# con_brd.net
KiCad netlist of a schematic drawn in EAGLE
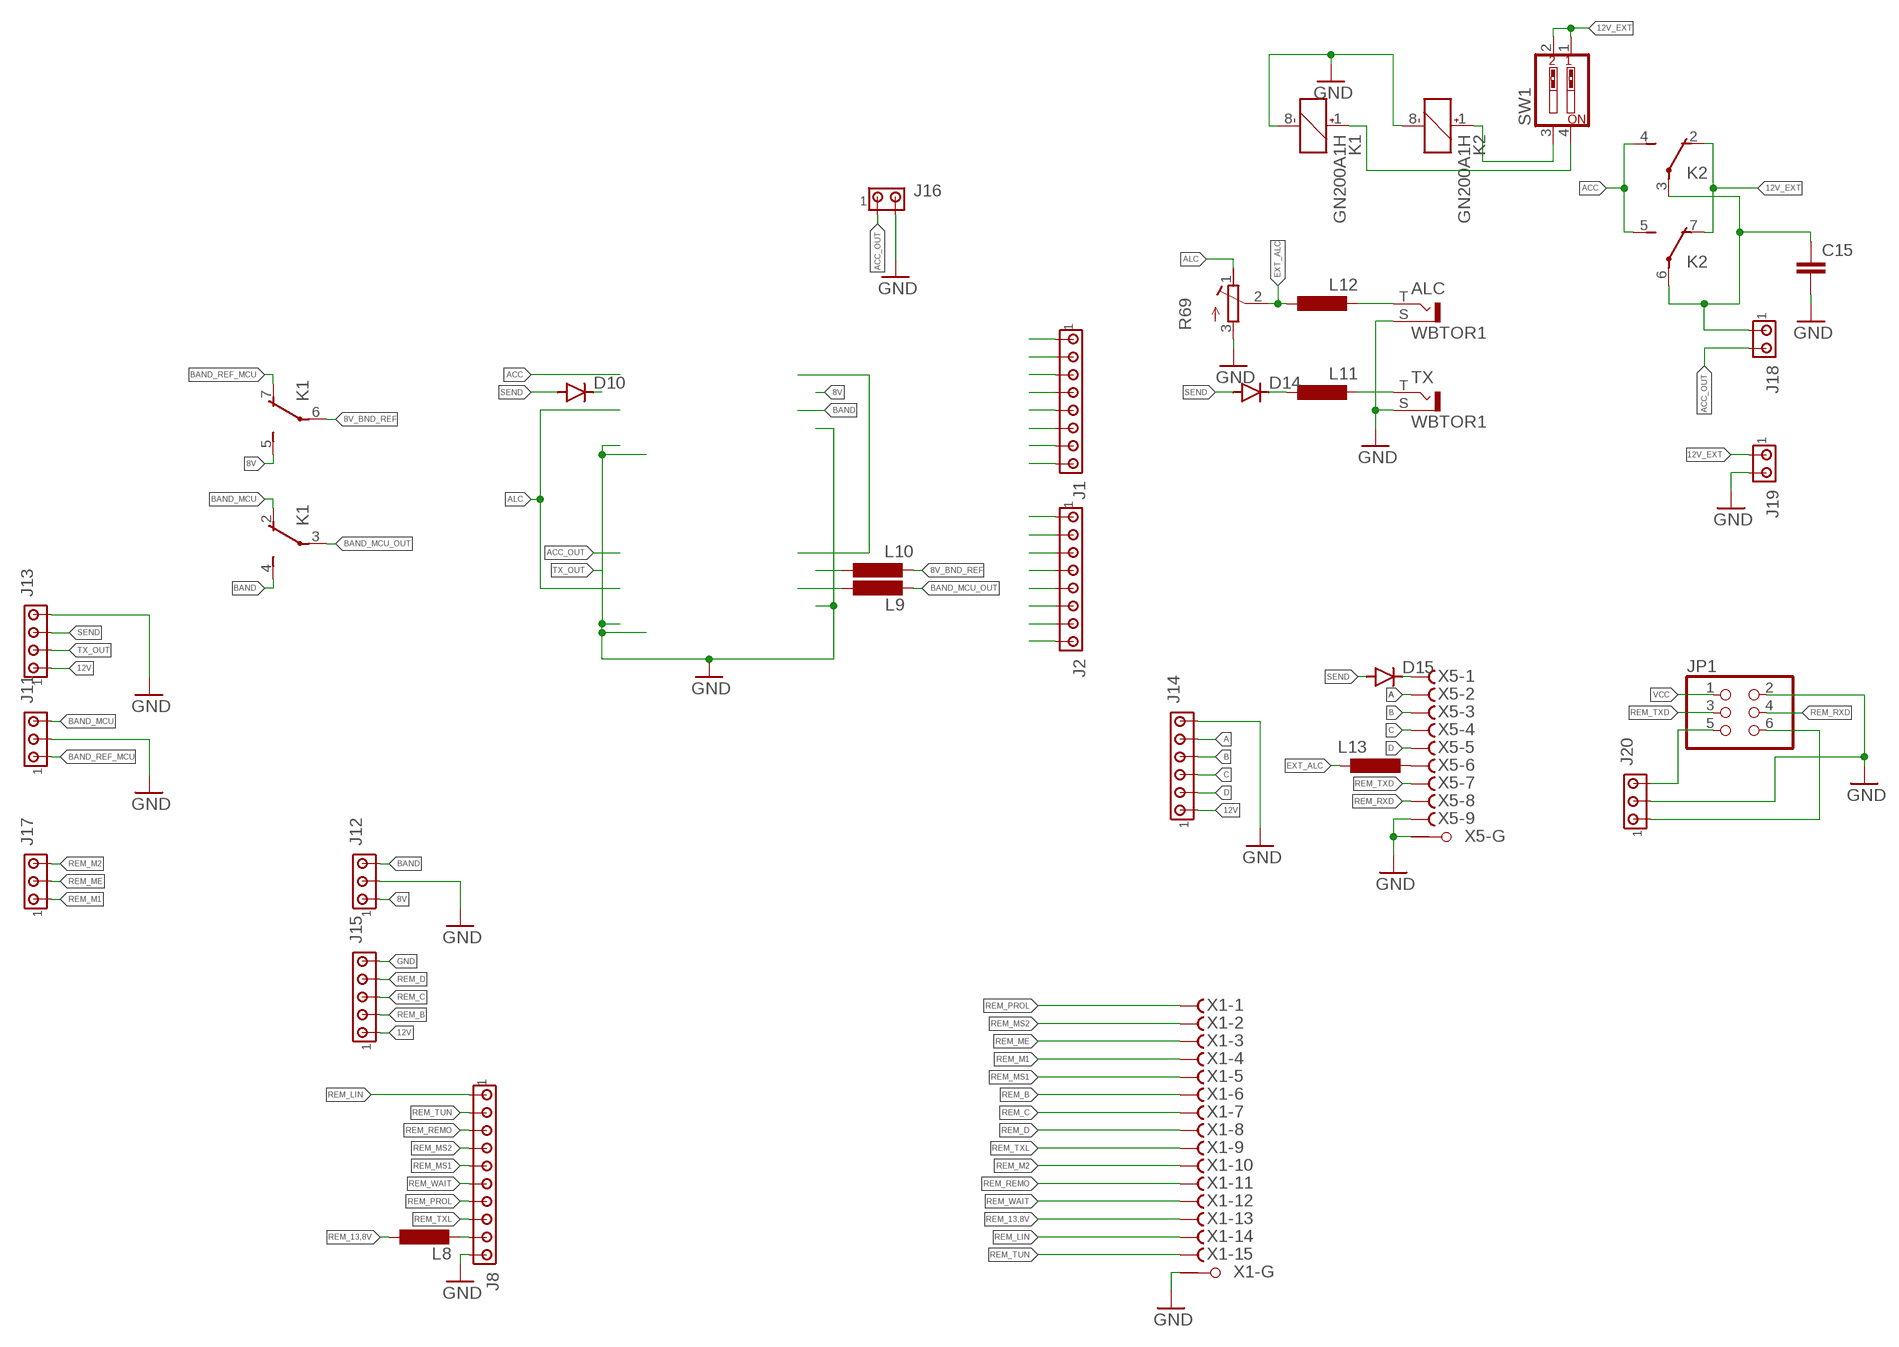
[diagram p0: schematic, sheet 1]

(export (version "E")
  (design (tool "Eeschema 10.0.6"))
  (components
    (comp (ref "ALC")
      (value "WBTOR1")
      (footprint "eagle-import:WBTOR1")
      (fields (field (name "MPN") "WBTOR 1 BLACK"))
      (libsource (lib "eagle-import") (part "WBTOR1"))
    )
    (comp (ref "C15")
      (value "C-EUC0805K")
      (footprint "eagle-import:C0805K")
      (libsource (lib "eagle-import") (part "C-EUC0805K"))
    )
    (comp (ref "D10")
      (value "DIODE-SOD123")
      (footprint "eagle-import:SOD123")
      (libsource (lib "eagle-import") (part "DIODE-SOD123"))
    )
    (comp (ref "D14")
      (value "DIODE-SOD123")
      (footprint "eagle-import:SOD123")
      (libsource (lib "eagle-import") (part "DIODE-SOD123"))
    )
    (comp (ref "D15")
      (value "DIODE-SOD123")
      (footprint "eagle-import:SOD123")
      (libsource (lib "eagle-import") (part "DIODE-SOD123"))
    )
    (comp (ref "J1")
      (value "MTA08-100")
      (footprint "eagle-import:10X08MTA")
      (libsource (lib "eagle-import") (part "MTA08-100"))
    )
    (comp (ref "J2")
      (value "MTA08-100")
      (footprint "eagle-import:10X08MTA")
      (libsource (lib "eagle-import") (part "MTA08-100"))
    )
    (comp (ref "J8")
      (value "MTA10-100")
      (footprint "eagle-import:10X10MTA")
      (libsource (lib "eagle-import") (part "MTA10-100"))
    )
    (comp (ref "J11")
      (value "MTA03-100")
      (footprint "eagle-import:10X03MTA")
      (libsource (lib "eagle-import") (part "MTA03-100"))
    )
    (comp (ref "J12")
      (value "MTA03-100")
      (footprint "eagle-import:10X03MTA")
      (libsource (lib "eagle-import") (part "MTA03-100"))
    )
    (comp (ref "J13")
      (value "MTA04-100")
      (footprint "eagle-import:10X04MTA")
      (libsource (lib "eagle-import") (part "MTA04-100"))
    )
    (comp (ref "J14")
      (value "MTA06-100")
      (footprint "eagle-import:10X06MTA")
      (libsource (lib "eagle-import") (part "MTA06-100"))
    )
    (comp (ref "J15")
      (value "MTA05-100")
      (footprint "eagle-import:10X05MTA")
      (libsource (lib "eagle-import") (part "MTA05-100"))
    )
    (comp (ref "J16")
      (value "MTA02-100")
      (footprint "eagle-import:10X02MTA")
      (libsource (lib "eagle-import") (part "MTA02-100"))
    )
    (comp (ref "J17")
      (value "MTA03-100")
      (footprint "eagle-import:10X03MTA")
      (libsource (lib "eagle-import") (part "MTA03-100"))
    )
    (comp (ref "J18")
      (value "MTA02-100")
      (footprint "eagle-import:10X02MTA")
      (libsource (lib "eagle-import") (part "MTA02-100"))
    )
    (comp (ref "J19")
      (value "MTA02-100")
      (footprint "eagle-import:10X02MTA")
      (libsource (lib "eagle-import") (part "MTA02-100"))
    )
    (comp (ref "J20")
      (value "MTA03-100")
      (footprint "eagle-import:10X03MTA")
      (libsource (lib "eagle-import") (part "MTA03-100"))
    )
    (comp (ref "JP1")
      (value "PINHD-2X3")
      (footprint "eagle-import:2X03")
      (libsource (lib "eagle-import") (part "PINHD-2X3"))
    )
    (comp (ref "K1")
      (value "GN200A1H")
      (footprint "eagle-import:GN-A")
      (libsource (lib "eagle-import") (part "GN?200A1H"))
    )
    (comp (ref "K2")
      (value "GN200A1H")
      (footprint "eagle-import:GN-A")
      (libsource (lib "eagle-import") (part "GN?200A1H"))
    )
    (comp (ref "L8")
      (value "L-EUL3230M")
      (footprint "eagle-import:L3230M")
      (libsource (lib "eagle-import") (part "L-EUL3230M"))
    )
    (comp (ref "L9")
      (value "L-EUL2012C")
      (footprint "eagle-import:L2012C")
      (libsource (lib "eagle-import") (part "L-EUL2012C"))
    )
    (comp (ref "L10")
      (value "L-EUL2012C")
      (footprint "eagle-import:L2012C")
      (libsource (lib "eagle-import") (part "L-EUL2012C"))
    )
    (comp (ref "L11")
      (value "L-EUL2012C")
      (footprint "eagle-import:L2012C")
      (libsource (lib "eagle-import") (part "L-EUL2012C"))
    )
    (comp (ref "L12")
      (value "L-EUL2012C")
      (footprint "eagle-import:L2012C")
      (libsource (lib "eagle-import") (part "L-EUL2012C"))
    )
    (comp (ref "L13")
      (value "L-EUL2012C")
      (footprint "eagle-import:L2012C")
      (libsource (lib "eagle-import") (part "L-EUL2012C"))
    )
    (comp (ref "R69")
      (value "R-TRIMM43P")
      (footprint "eagle-import:RTRIM43P")
      (libsource (lib "eagle-import") (part "R-TRIMM43P"))
    )
    (comp (ref "SW1")
      (value "SW_DIP-2")
      (footprint "eagle-import:EDG-02")
      (libsource (lib "eagle-import") (part "SW_DIP-2"))
    )
    (comp (ref "TX")
      (value "WBTOR1")
      (footprint "eagle-import:WBTOR1")
      (fields (field (name "MPN") "WBTOR 1 BLACK"))
      (libsource (lib "eagle-import") (part "WBTOR1"))
    )
    (comp (ref "X1")
      (value "F15HPS")
      (footprint "eagle-import:F15HP")
      (libsource (lib "eagle-import") (part "F15HPS"))
    )
    (comp (ref "X5")
      (value "F09HPS")
      (footprint "eagle-import:F09HP")
      (libsource (lib "eagle-import") (part "F09HPS"))
    )
  )
  (nets
    (net (code "1") (name "/N$71") (class "Default")
      (node (ref "J1") (pin "6") (pinfunction "6_6") (pintype "passive"))
      (node (ref "J2") (pin "6") (pinfunction "6_6") (pintype "passive"))
    )
    (net (code "2") (name "/N$72") (class "Default")
      (node (ref "J2") (pin "4") (pinfunction "4_4") (pintype "passive"))
      (node (ref "L9") (pin "1") (pinfunction "1_1") (pintype "passive"))
    )
    (net (code "3") (name "/N$75") (class "Default")
      (node (ref "J2") (pin "1") (pinfunction "1_1") (pintype "passive"))
      (node (ref "L10") (pin "1") (pinfunction "1_1") (pintype "passive"))
    )
    (net (code "4") (name "/N$79") (class "Default")
      (node (ref "D10") (pin "C") (pinfunction "C_C") (pintype "passive"))
      (node (ref "J1") (pin "3") (pinfunction "3_3") (pintype "passive"))
    )
    (net (code "5") (name "8V") (class "Default")
      (node (ref "J1") (pin "1") (pinfunction "1_1") (pintype "passive"))
      (node (ref "J12") (pin "1") (pinfunction "1_1") (pintype "passive"))
      (node (ref "K1") (pin "5") (pinfunction "S_5") (pintype "passive"))
    )
    (net (code "6") (name "8V_BND_REF") (class "Default")
      (node (ref "K1") (pin "6") (pinfunction "P_6") (pintype "passive"))
      (node (ref "L10") (pin "2") (pinfunction "2_2") (pintype "passive"))
    )
    (net (code "7") (name "12V") (class "Default")
      (node (ref "J13") (pin "1") (pinfunction "1_1") (pintype "passive"))
      (node (ref "J14") (pin "1") (pinfunction "1_1") (pintype "passive"))
      (node (ref "J15") (pin "1") (pinfunction "1_1") (pintype "passive"))
    )
    (net (code "8") (name "12V_EXT") (class "Default")
      (node (ref "J19") (pin "1") (pinfunction "1_1") (pintype "passive"))
      (node (ref "K2") (pin "2") (pinfunction "O_2") (pintype "passive"))
      (node (ref "K2") (pin "7") (pinfunction "O_7") (pintype "passive"))
      (node (ref "SW1") (pin "1") (pinfunction "1_1") (pintype "passive"))
      (node (ref "SW1") (pin "2") (pinfunction "2_2") (pintype "passive"))
    )
    (net (code "9") (name "A") (class "Default")
      (node (ref "J14") (pin "5") (pinfunction "5_5") (pintype "passive"))
      (node (ref "X5") (pin "2") (pinfunction "F_2") (pintype "passive"))
    )
    (net (code "10") (name "ACC") (class "Default")
      (node (ref "J1") (pin "7") (pinfunction "7_7") (pintype "passive"))
      (node (ref "K2") (pin "4") (pinfunction "S_4") (pintype "passive"))
      (node (ref "K2") (pin "5") (pinfunction "S_5") (pintype "passive"))
    )
    (net (code "11") (name "ACC_OUT") (class "Default")
      (node (ref "J16") (pin "1") (pinfunction "1_1") (pintype "passive"))
      (node (ref "J18") (pin "2") (pinfunction "2_2") (pintype "passive"))
      (node (ref "J2") (pin "7") (pinfunction "7_7") (pintype "passive"))
    )
    (net (code "12") (name "ALC") (class "Default")
      (node (ref "J1") (pin "5") (pinfunction "5_5") (pintype "passive"))
      (node (ref "J2") (pin "5") (pinfunction "5_5") (pintype "passive"))
      (node (ref "R69") (pin "1") (pinfunction "E_1") (pintype "passive"))
    )
    (net (code "13") (name "B") (class "Default")
      (node (ref "J14") (pin "4") (pinfunction "4_4") (pintype "passive"))
      (node (ref "X5") (pin "3") (pinfunction "F_3") (pintype "passive"))
    )
    (net (code "14") (name "BAND") (class "Default")
      (node (ref "J1") (pin "4") (pinfunction "4_4") (pintype "passive"))
      (node (ref "J12") (pin "3") (pinfunction "3_3") (pintype "passive"))
      (node (ref "K1") (pin "4") (pinfunction "S_4") (pintype "passive"))
    )
    (net (code "15") (name "BAND_MCU") (class "Default")
      (node (ref "J11") (pin "3") (pinfunction "3_3") (pintype "passive"))
      (node (ref "K1") (pin "2") (pinfunction "O_2") (pintype "passive"))
    )
    (net (code "16") (name "BAND_MCU_OUT") (class "Default")
      (node (ref "K1") (pin "3") (pinfunction "P_3") (pintype "passive"))
      (node (ref "L9") (pin "2") (pinfunction "2_2") (pintype "passive"))
    )
    (net (code "17") (name "BAND_REF_MCU") (class "Default")
      (node (ref "J11") (pin "1") (pinfunction "1_1") (pintype "passive"))
      (node (ref "K1") (pin "7") (pinfunction "O_7") (pintype "passive"))
    )
    (net (code "18") (name "C") (class "Default")
      (node (ref "J14") (pin "3") (pinfunction "3_3") (pintype "passive"))
      (node (ref "X5") (pin "4") (pinfunction "F_4") (pintype "passive"))
    )
    (net (code "19") (name "D") (class "Default")
      (node (ref "J14") (pin "2") (pinfunction "2_2") (pintype "passive"))
      (node (ref "X5") (pin "5") (pinfunction "F_5") (pintype "passive"))
    )
    (net (code "20") (name "EXT_ALC") (class "Default")
      (node (ref "L12") (pin "1") (pinfunction "1_1") (pintype "passive"))
      (node (ref "L13") (pin "1") (pinfunction "1_1") (pintype "passive"))
      (node (ref "R69") (pin "2") (pinfunction "S_2") (pintype "passive"))
    )
    (net (code "21") (name "GND") (class "Default")
      (node (ref "ALC") (pin "S") (pinfunction "S_S") (pintype "passive"))
      (node (ref "C15") (pin "2") (pinfunction "2_2") (pintype "passive"))
      (node (ref "J1") (pin "2") (pinfunction "2_2") (pintype "passive"))
      (node (ref "J1") (pin "8") (pinfunction "8_8") (pintype "passive"))
      (node (ref "J11") (pin "2") (pinfunction "2_2") (pintype "passive"))
      (node (ref "J12") (pin "2") (pinfunction "2_2") (pintype "passive"))
      (node (ref "J13") (pin "4") (pinfunction "4_4") (pintype "passive"))
      (node (ref "J14") (pin "6") (pinfunction "6_6") (pintype "passive"))
      (node (ref "J15") (pin "5") (pinfunction "5_5") (pintype "passive"))
      (node (ref "J16") (pin "2") (pinfunction "2_2") (pintype "passive"))
      (node (ref "J19") (pin "2") (pinfunction "2_2") (pintype "passive"))
      (node (ref "J2") (pin "2") (pinfunction "2_2") (pintype "passive"))
      (node (ref "J2") (pin "8") (pinfunction "8_8") (pintype "passive"))
      (node (ref "J20") (pin "2") (pinfunction "2_2") (pintype "passive"))
      (node (ref "J8") (pin "10") (pinfunction "10_10") (pintype "passive"))
      (node (ref "JP1") (pin "2") (pinfunction "2_2") (pintype "passive"))
      (node (ref "K1") (pin "8") (pinfunction "-_8") (pintype "passive"))
      (node (ref "K2") (pin "8") (pinfunction "-_8") (pintype "passive"))
      (node (ref "R69") (pin "3") (pinfunction "A_3") (pintype "passive"))
      (node (ref "TX") (pin "S") (pinfunction "S_S") (pintype "passive"))
      (node (ref "X1") (pin "G1") (pinfunction "G1_G1") (pintype "passive"))
      (node (ref "X5") (pin "9") (pinfunction "F_9") (pintype "passive"))
      (node (ref "X5") (pin "G1") (pinfunction "G1_G1") (pintype "passive"))
    )
    (net (code "22") (name "Net-(ALC-PadT)") (class "Default")
      (node (ref "ALC") (pin "T") (pinfunction "T_T") (pintype "passive"))
      (node (ref "L12") (pin "2") (pinfunction "2_2") (pintype "passive"))
    )
    (net (code "23") (name "Net-(D14-PadC)") (class "Default")
      (node (ref "D14") (pin "C") (pinfunction "C_C") (pintype "passive"))
      (node (ref "L11") (pin "1") (pinfunction "1_1") (pintype "passive"))
    )
    (net (code "24") (name "Net-(J8-Pad9)") (class "Default")
      (node (ref "J8") (pin "9") (pinfunction "9_9") (pintype "passive"))
      (node (ref "L8") (pin "2") (pinfunction "2_2") (pintype "passive"))
    )
    (net (code "25") (name "Net-(J20-Pad1)") (class "Default")
      (node (ref "J20") (pin "1") (pinfunction "1_1") (pintype "passive"))
      (node (ref "JP1") (pin "6") (pinfunction "6_6") (pintype "passive"))
    )
    (net (code "26") (name "Net-(J20-Pad3)") (class "Default")
      (node (ref "J20") (pin "3") (pinfunction "3_3") (pintype "passive"))
      (node (ref "JP1") (pin "5") (pinfunction "5_5") (pintype "passive"))
    )
    (net (code "27") (name "Net-(K1A-+)") (class "Default")
      (node (ref "K1") (pin "1") (pinfunction "+_1") (pintype "passive"))
      (node (ref "SW1") (pin "4") (pinfunction "4_4") (pintype "passive"))
    )
    (net (code "28") (name "Net-(K2A-+)") (class "Default")
      (node (ref "K2") (pin "1") (pinfunction "+_1") (pintype "passive"))
      (node (ref "SW1") (pin "3") (pinfunction "3_3") (pintype "passive"))
    )
    (net (code "29") (name "Net-(L11-Pad2)") (class "Default")
      (node (ref "L11") (pin "2") (pinfunction "2_2") (pintype "passive"))
      (node (ref "TX") (pin "T") (pinfunction "T_T") (pintype "passive"))
    )
    (net (code "30") (name "Net-(X5A-F)") (class "Default")
      (node (ref "D15") (pin "C") (pinfunction "C_C") (pintype "passive"))
      (node (ref "X5") (pin "1") (pinfunction "F_1") (pintype "passive"))
    )
    (net (code "31") (name "Net-(X5F-F)") (class "Default")
      (node (ref "L13") (pin "2") (pinfunction "2_2") (pintype "passive"))
      (node (ref "X5") (pin "6") (pinfunction "F_6") (pintype "passive"))
    )
    (net (code "32") (name "REM_13,8V") (class "Default")
      (node (ref "L8") (pin "1") (pinfunction "1_1") (pintype "passive"))
      (node (ref "X1") (pin "13") (pinfunction "F_13") (pintype "passive"))
    )
    (net (code "33") (name "REM_B") (class "Default")
      (node (ref "J15") (pin "2") (pinfunction "2_2") (pintype "passive"))
      (node (ref "X1") (pin "6") (pinfunction "F_6") (pintype "passive"))
    )
    (net (code "34") (name "REM_C") (class "Default")
      (node (ref "J15") (pin "3") (pinfunction "3_3") (pintype "passive"))
      (node (ref "X1") (pin "7") (pinfunction "F_7") (pintype "passive"))
    )
    (net (code "35") (name "REM_D") (class "Default")
      (node (ref "J15") (pin "4") (pinfunction "4_4") (pintype "passive"))
      (node (ref "X1") (pin "8") (pinfunction "F_8") (pintype "passive"))
    )
    (net (code "36") (name "REM_LIN") (class "Default")
      (node (ref "J8") (pin "1") (pinfunction "1_1") (pintype "passive"))
      (node (ref "X1") (pin "14") (pinfunction "F_14") (pintype "passive"))
    )
    (net (code "37") (name "REM_M1") (class "Default")
      (node (ref "J17") (pin "1") (pinfunction "1_1") (pintype "passive"))
      (node (ref "X1") (pin "4") (pinfunction "F_4") (pintype "passive"))
    )
    (net (code "38") (name "REM_M2") (class "Default")
      (node (ref "J17") (pin "3") (pinfunction "3_3") (pintype "passive"))
      (node (ref "X1") (pin "10") (pinfunction "F_10") (pintype "passive"))
    )
    (net (code "39") (name "REM_ME") (class "Default")
      (node (ref "J17") (pin "2") (pinfunction "2_2") (pintype "passive"))
      (node (ref "X1") (pin "3") (pinfunction "F_3") (pintype "passive"))
    )
    (net (code "40") (name "REM_MS1") (class "Default")
      (node (ref "J8") (pin "5") (pinfunction "5_5") (pintype "passive"))
      (node (ref "X1") (pin "5") (pinfunction "F_5") (pintype "passive"))
    )
    (net (code "41") (name "REM_MS2") (class "Default")
      (node (ref "J8") (pin "4") (pinfunction "4_4") (pintype "passive"))
      (node (ref "X1") (pin "2") (pinfunction "F_2") (pintype "passive"))
    )
    (net (code "42") (name "REM_PROL") (class "Default")
      (node (ref "J8") (pin "7") (pinfunction "7_7") (pintype "passive"))
      (node (ref "X1") (pin "1") (pinfunction "F_1") (pintype "passive"))
    )
    (net (code "43") (name "REM_REMO") (class "Default")
      (node (ref "J8") (pin "3") (pinfunction "3_3") (pintype "passive"))
      (node (ref "X1") (pin "11") (pinfunction "F_11") (pintype "passive"))
    )
    (net (code "44") (name "REM_RXD") (class "Default")
      (node (ref "JP1") (pin "4") (pinfunction "4_4") (pintype "passive"))
      (node (ref "X5") (pin "8") (pinfunction "F_8") (pintype "passive"))
    )
    (net (code "45") (name "REM_TUN") (class "Default")
      (node (ref "J8") (pin "2") (pinfunction "2_2") (pintype "passive"))
      (node (ref "X1") (pin "15") (pinfunction "F_15") (pintype "passive"))
    )
    (net (code "46") (name "REM_TXD") (class "Default")
      (node (ref "JP1") (pin "3") (pinfunction "3_3") (pintype "passive"))
      (node (ref "X5") (pin "7") (pinfunction "F_7") (pintype "passive"))
    )
    (net (code "47") (name "REM_TXL") (class "Default")
      (node (ref "J8") (pin "8") (pinfunction "8_8") (pintype "passive"))
      (node (ref "X1") (pin "9") (pinfunction "F_9") (pintype "passive"))
    )
    (net (code "48") (name "REM_WAIT") (class "Default")
      (node (ref "J8") (pin "6") (pinfunction "6_6") (pintype "passive"))
      (node (ref "X1") (pin "12") (pinfunction "F_12") (pintype "passive"))
    )
    (net (code "49") (name "SEND") (class "Default")
      (node (ref "D10") (pin "A") (pinfunction "A_A") (pintype "passive"))
      (node (ref "D14") (pin "A") (pinfunction "A_A") (pintype "passive"))
      (node (ref "D15") (pin "A") (pinfunction "A_A") (pintype "passive"))
      (node (ref "J13") (pin "3") (pinfunction "3_3") (pintype "passive"))
    )
    (net (code "50") (name "TX_OUT") (class "Default")
      (node (ref "J13") (pin "2") (pinfunction "2_2") (pintype "passive"))
      (node (ref "J2") (pin "3") (pinfunction "3_3") (pintype "passive"))
    )
    (net (code "51") (name "VCC") (class "Default")
      (node (ref "C15") (pin "1") (pinfunction "1_1") (pintype "passive"))
      (node (ref "J18") (pin "1") (pinfunction "1_1") (pintype "passive"))
      (node (ref "JP1") (pin "1") (pinfunction "1_1") (pintype "passive"))
      (node (ref "K2") (pin "3") (pinfunction "P_3") (pintype "passive"))
      (node (ref "K2") (pin "6") (pinfunction "P_6") (pintype "passive"))
    )
    (net (code "52") (name "unconnected-(X1-PadG2)") (class "Default")
      (node (ref "X1") (pin "G2") (pinfunction "G2_G2") (pintype "passive"))
    )
    (net (code "53") (name "unconnected-(X5-PadG2)") (class "Default")
      (node (ref "X5") (pin "G2") (pinfunction "G2_G2") (pintype "passive"))
    )
  )
)
